# Sheet_CL-PFC-01.net
KiCad netlist of a schematic drawn in Altium Designer
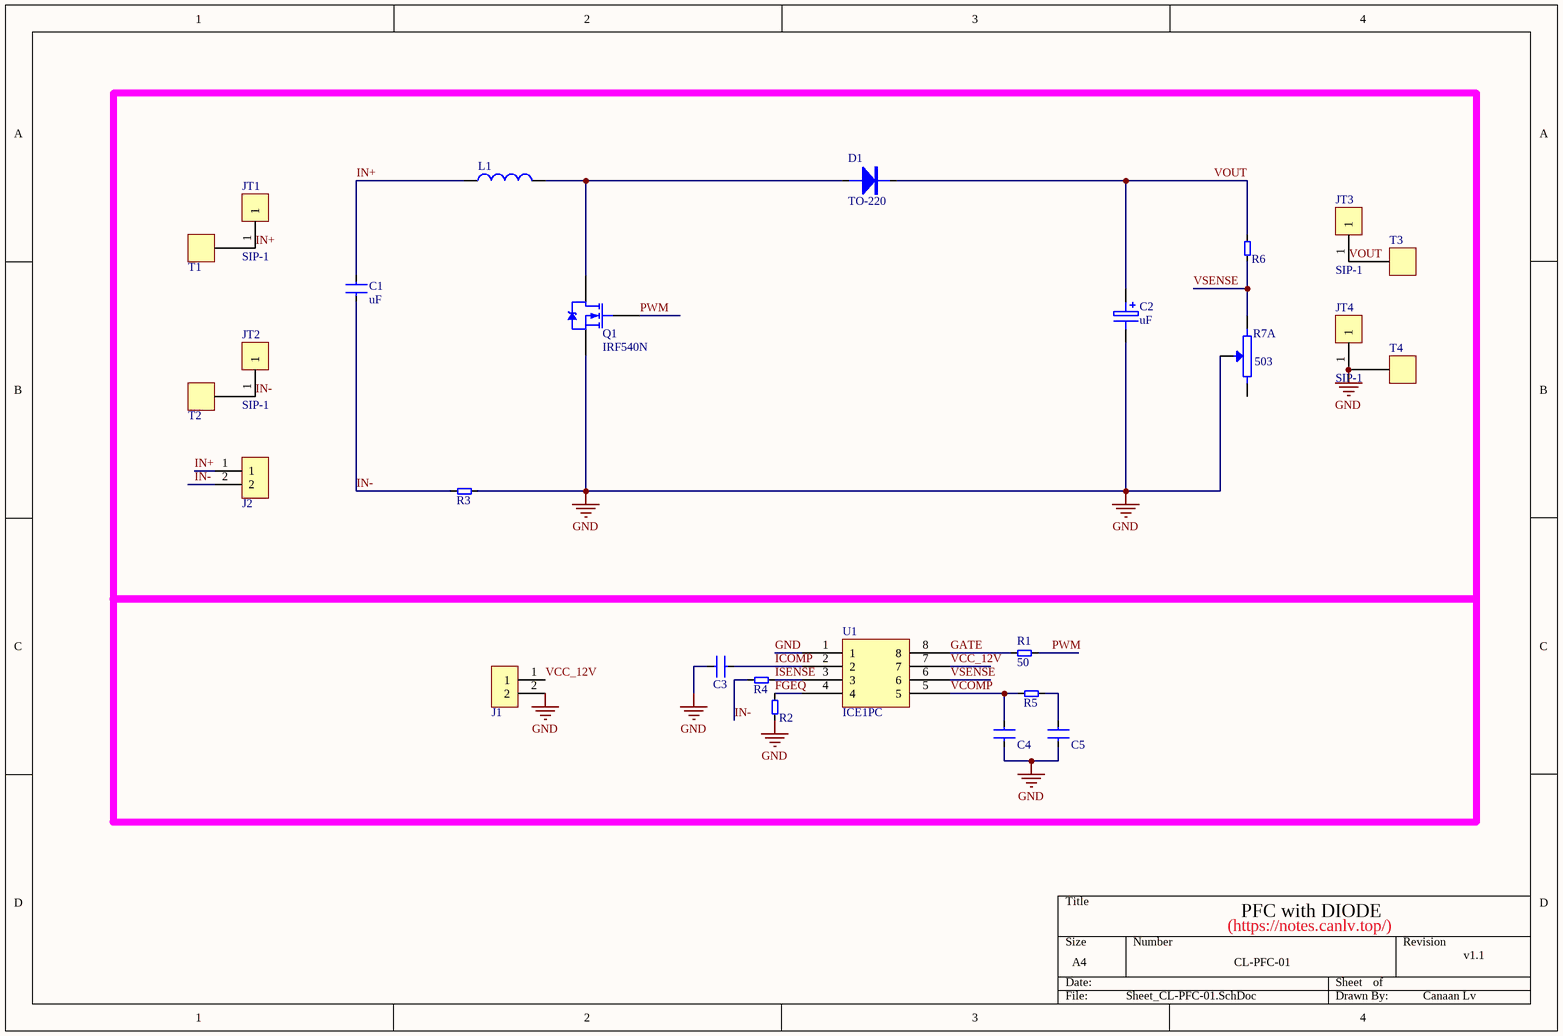
[diagram p0: Sheet_CL-PFC-01.SchDoc]

(export (version "E")
  (design (tool "Eeschema 10.0.6"))
  (components
    (comp (ref "C1") (value "uF") (footprint "CAP-7.5-CP") (libsource (lib "电容") (part "C直插无极性")))
    (comp (ref "C2") (value "uF") (footprint "CZ18X35") (libsource (lib "电容") (part "C直插电容")))
    (comp (ref "C3") (value "uF") (footprint "C120603") (libsource (lib "电容") (part "C贴片电容")))
    (comp (ref "C4") (value "uF") (footprint "C120603") (libsource (lib "电容") (part "C贴片电容")))
    (comp (ref "C5") (value "uF") (footprint "C120603") (libsource (lib "电容") (part "C贴片电容")))
    (comp (ref "D1") (value "TO-220") (footprint "TO-220") (libsource (lib "二极管") (part "TO-220")))
    (comp (ref "J1") (value "SIP-2") (footprint "2.54XH接插件2P") (libsource (lib "接插件") (part "SIP-2")))
    (comp (ref "J2") (value "SIP-2") (footprint "2.54XH接插件2P") (libsource (lib "") (part "SIP-2_1")))
    (comp (ref "JT1") (value "SIP-1") (footprint "2.54排针1X1") (libsource (lib "接插件") (part "SIP-1")))
    (comp (ref "JT2") (value "SIP-1") (footprint "2.54排针1X1") (libsource (lib "接插件") (part "SIP-1")))
    (comp (ref "JT3") (value "SIP-1") (footprint "2.54排针1X1") (libsource (lib "接插件") (part "SIP-1")))
    (comp (ref "JT4") (value "SIP-1") (footprint "2.54排针1X1") (libsource (lib "接插件") (part "SIP-1")))
    (comp (ref "L1") (value "~") (footprint "77930") (libsource (lib "电感") (part "直插电感")))
    (comp (ref "Q1")
      (value "IRF540N")
      (footprint "TO-220AB")
      (description "HEXFET Power MOSFET")
      (fields (field (name "PUBLISHER") "Altium Limited"))
      (libsource (lib "IR Discrete MOSFET - Power") (part "IRF540N"))
    )
    (comp (ref "R1")
      (value "R贴片电阻")
      (footprint "R120603")
      (fields (field (name "ALTIUM_UNNAMED_1") "50"))
      (libsource (lib "电阻") (part "R贴片电阻"))
    )
    (comp (ref "R2") (value "R贴片电阻") (footprint "R120603") (libsource (lib "电阻") (part "R贴片电阻")))
    (comp (ref "R3") (value "R直插电阻") (footprint "水泥电阻") (libsource (lib "电阻") (part "R直插电阻")))
    (comp (ref "R4") (value "R贴片电阻") (footprint "R120603") (libsource (lib "电阻") (part "R贴片电阻")))
    (comp (ref "R5") (value "R贴片电阻") (footprint "R120603") (libsource (lib "电阻") (part "R贴片电阻")))
    (comp (ref "R6") (value "R贴片电阻") (footprint "R120603") (libsource (lib "电阻") (part "R贴片电阻")))
    (comp (ref "R7")
      (value "~")
      (footprint "ADJ-3296-1")
      (fields (field (name "ALTIUM_UNNAMED_1") "503"))
      (libsource (lib "电阻") (part "R电位器"))
    )
    (comp (ref "T1") (value "香蕉头接线柱") (footprint "香蕉接线柱Black_6mm") (libsource (lib "") (part "香蕉头接线柱_1")))
    (comp (ref "T2") (value "香蕉头接线柱") (footprint "香蕉接线柱Black_6mm") (libsource (lib "") (part "香蕉头接线柱_1")))
    (comp (ref "T3") (value "香蕉头接线柱") (footprint "香蕉接线柱Black_6mm") (libsource (lib "接插件") (part "香蕉头接线柱")))
    (comp (ref "T4") (value "香蕉头接线柱") (footprint "香蕉接线柱Black_6mm") (libsource (lib "接插件") (part "香蕉头接线柱")))
    (comp (ref "U1") (value "ICE1PC") (footprint "SOP8") (libsource (lib "集成块") (part "IC8")))
  )
  (nets
    (net (code "1") (name "/FGEQ") (class "Default")
      (node (ref "R2") (pin "2") (pinfunction "2_2") (pintype "passive"))
      (node (ref "U1") (pin "4") (pinfunction "4_4") (pintype "passive"))
    )
    (net (code "2") (name "/GATE") (class "Default")
      (node (ref "R1") (pin "1") (pinfunction "1_1") (pintype "passive"))
      (node (ref "U1") (pin "8") (pinfunction "8_8") (pintype "passive"))
    )
    (net (code "3") (name "/ICOMP") (class "Default")
      (node (ref "C3") (pin "2") (pinfunction "2_2") (pintype "passive"))
      (node (ref "U1") (pin "2") (pinfunction "2_2") (pintype "passive"))
    )
    (net (code "4") (name "/IN+") (class "Default")
      (node (ref "C1") (pin "1") (pinfunction "1_1") (pintype "passive"))
      (node (ref "J2") (pin "1") (pinfunction "1_1") (pintype "passive"))
      (node (ref "JT1") (pin "1") (pinfunction "1_1") (pintype "passive"))
      (node (ref "L1") (pin "1") (pinfunction "1_1") (pintype "passive"))
      (node (ref "T1") (pin "1") (pinfunction "1_1") (pintype "passive"))
    )
    (net (code "5") (name "/IN-") (class "Default")
      (node (ref "C1") (pin "2") (pinfunction "2_2") (pintype "passive"))
      (node (ref "J2") (pin "2") (pinfunction "2_2") (pintype "passive"))
      (node (ref "JT2") (pin "1") (pinfunction "1_1") (pintype "passive"))
      (node (ref "R3") (pin "1") (pinfunction "1_1") (pintype "passive"))
      (node (ref "R4") (pin "2") (pinfunction "2_2") (pintype "passive"))
      (node (ref "T2") (pin "1") (pinfunction "1_1") (pintype "passive"))
    )
    (net (code "6") (name "/ISENSE") (class "Default")
      (node (ref "R4") (pin "1") (pinfunction "1_1") (pintype "passive"))
      (node (ref "U1") (pin "3") (pinfunction "3_3") (pintype "passive"))
    )
    (net (code "7") (name "/PWM") (class "Default")
      (node (ref "Q1") (pin "1") (pinfunction "G_1") (pintype "passive"))
      (node (ref "R1") (pin "2") (pinfunction "2_2") (pintype "passive"))
    )
    (net (code "8") (name "/VCC_12V") (class "Default")
      (node (ref "J1") (pin "1") (pinfunction "1_1") (pintype "passive"))
      (node (ref "U1") (pin "7") (pinfunction "7_7") (pintype "passive"))
    )
    (net (code "9") (name "/VCOMP") (class "Default")
      (node (ref "C4") (pin "2") (pinfunction "2_2") (pintype "passive"))
      (node (ref "R5") (pin "2") (pinfunction "2_2") (pintype "passive"))
      (node (ref "U1") (pin "5") (pinfunction "5_5") (pintype "passive"))
    )
    (net (code "10") (name "/VOUT") (class "Default")
      (node (ref "C2") (pin "1") (pinfunction "1_1") (pintype "passive"))
      (node (ref "D1") (pin "K") (pinfunction "2_K") (pintype "passive"))
      (node (ref "JT3") (pin "1") (pinfunction "1_1") (pintype "passive"))
      (node (ref "R6") (pin "1") (pinfunction "1_1") (pintype "passive"))
      (node (ref "T3") (pin "1") (pinfunction "1_1") (pintype "passive"))
    )
    (net (code "11") (name "/VSENSE") (class "Default")
      (node (ref "R6") (pin "2") (pinfunction "2_2") (pintype "passive"))
      (node (ref "R7") (pin "1") (pinfunction "1_1") (pintype "passive"))
      (node (ref "U1") (pin "6") (pinfunction "6_6") (pintype "passive"))
    )
    (net (code "12") (name "GND") (class "Default")
      (node (ref "C2") (pin "2") (pinfunction "2_2") (pintype "passive"))
      (node (ref "C3") (pin "1") (pinfunction "1_1") (pintype "passive"))
      (node (ref "C4") (pin "1") (pinfunction "1_1") (pintype "passive"))
      (node (ref "C5") (pin "1") (pinfunction "1_1") (pintype "passive"))
      (node (ref "J1") (pin "2") (pinfunction "2_2") (pintype "passive"))
      (node (ref "JT4") (pin "1") (pinfunction "1_1") (pintype "passive"))
      (node (ref "Q1") (pin "3") (pinfunction "S_3") (pintype "passive"))
      (node (ref "R2") (pin "1") (pinfunction "1_1") (pintype "passive"))
      (node (ref "R3") (pin "2") (pinfunction "2_2") (pintype "passive"))
      (node (ref "R7") (pin "2") (pinfunction "2_2") (pintype "passive"))
      (node (ref "T4") (pin "1") (pinfunction "1_1") (pintype "passive"))
      (node (ref "U1") (pin "1") (pinfunction "1_1") (pintype "passive"))
    )
    (net (code "13") (name "Net-(C5-Pad2)") (class "Default")
      (node (ref "C5") (pin "2") (pinfunction "2_2") (pintype "passive"))
      (node (ref "R5") (pin "1") (pinfunction "1_1") (pintype "passive"))
    )
    (net (code "14") (name "Net-(D1-1)") (class "Default")
      (node (ref "D1") (pin "A") (pinfunction "1_A") (pintype "passive"))
      (node (ref "L1") (pin "2") (pinfunction "2_2") (pintype "passive"))
      (node (ref "Q1") (pin "2") (pinfunction "D_2") (pintype "passive"))
    )
    (net (code "15") (name "unconnected-(R7-Pad3)") (class "Default")
      (node (ref "R7") (pin "3") (pinfunction "3_3") (pintype "passive"))
    )
  )
)
